# Power_24V.net
KiCad netlist of a schematic drawn in Altium Designer
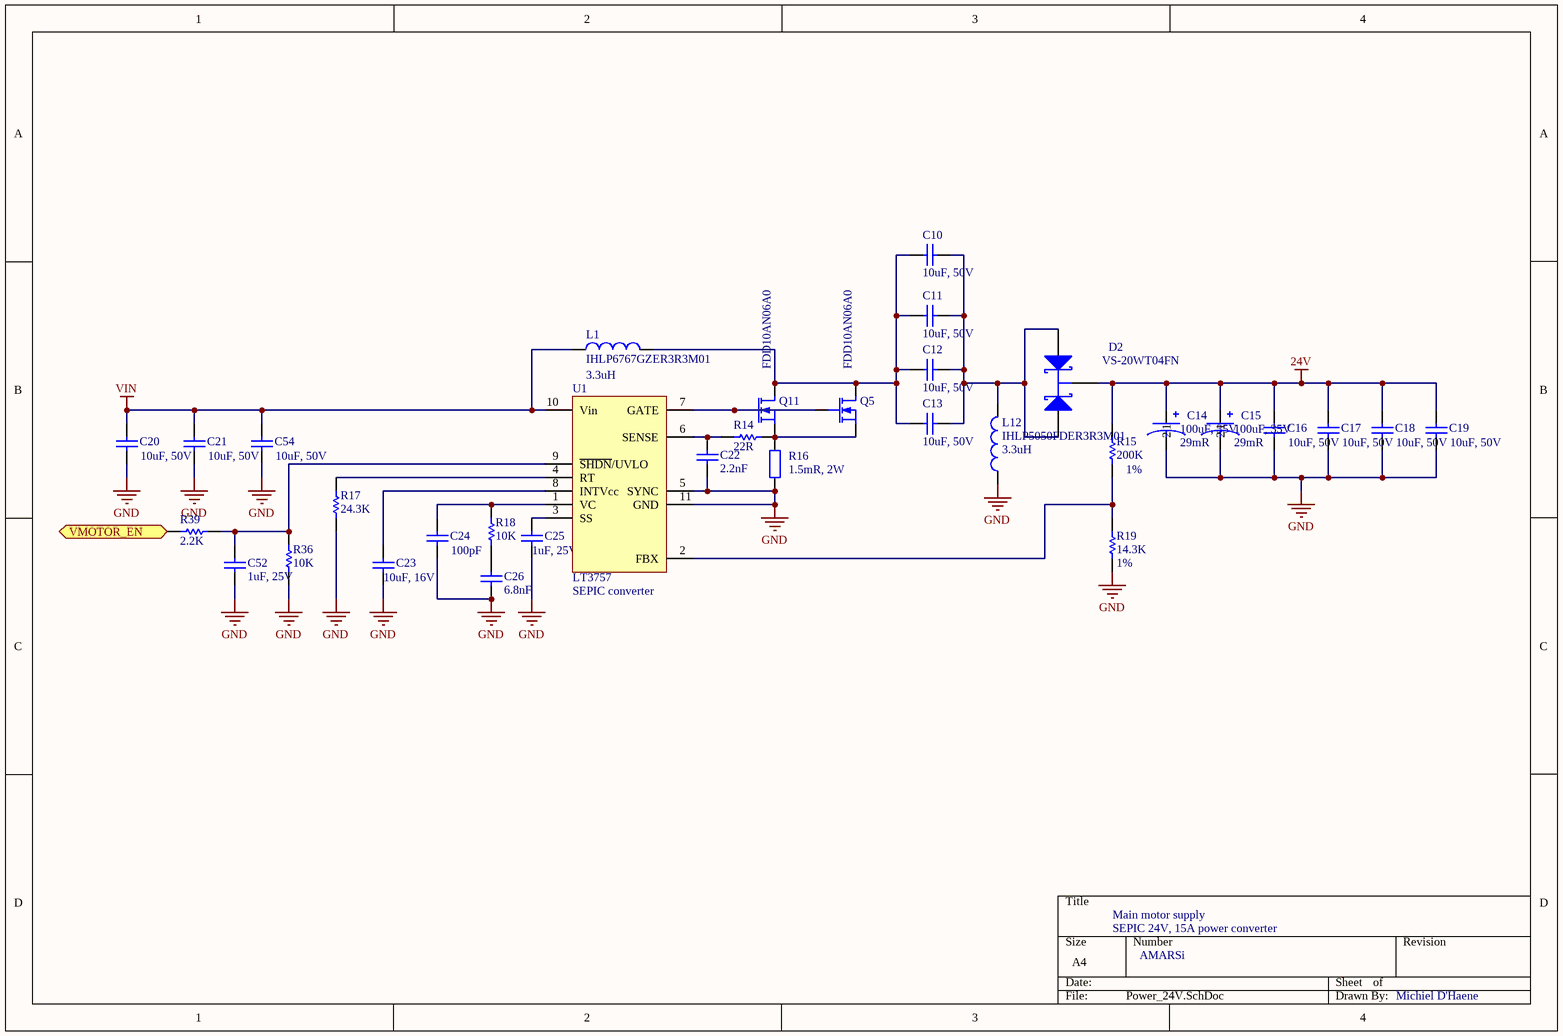
[diagram p0: Power_24V.SchDoc]

(export (version "E")
  (design (tool "Eeschema 10.0.6"))
  (components
    (comp (ref "C10")
      (value "10uF, 50V")
      (footprint "CAPC3216L")
      (description "Capacitor (Semiconductor SIM Model)")
      (fields (field (name "VOLTAGE") "50V") (field (name "PUBLISHER") "Altium Limited"))
      (libsource (lib "Miscellaneous Devices") (part "Cap Semi"))
    )
    (comp (ref "C11")
      (value "10uF, 50V")
      (footprint "CAPC3216L")
      (description "Capacitor (Semiconductor SIM Model)")
      (fields (field (name "VOLTAGE") "50V") (field (name "PUBLISHER") "Altium Limited"))
      (libsource (lib "Miscellaneous Devices") (part "Cap Semi"))
    )
    (comp (ref "C12")
      (value "10uF, 50V")
      (footprint "CAPC3216L")
      (description "Capacitor (Semiconductor SIM Model)")
      (fields (field (name "VOLTAGE") "50V") (field (name "PUBLISHER") "Altium Limited"))
      (libsource (lib "Miscellaneous Devices") (part "Cap Semi"))
    )
    (comp (ref "C13")
      (value "10uF, 50V")
      (footprint "CAPC3216L")
      (description "Capacitor (Semiconductor SIM Model)")
      (fields (field (name "VOLTAGE") "50V") (field (name "PUBLISHER") "Altium Limited"))
      (libsource (lib "Miscellaneous Devices") (part "Cap Semi"))
    )
    (comp (ref "C14")
      (value "100uF, 35V")
      (footprint "CAP_POL_SMD_SIZE_G")
      (fields (field (name "ESR") "29mR") (field (name "Comment") "100uF, 35V, 29mR"))
      (libsource (lib "New_library") (part "CAP_POL"))
    )
    (comp (ref "C15")
      (value "100uF, 35V")
      (footprint "CAP_POL_SMD_SIZE_G")
      (fields (field (name "ESR") "29mR") (field (name "Comment") "100uF, 35V, 29mR"))
      (libsource (lib "New_library") (part "CAP_POL"))
    )
    (comp (ref "C16")
      (value "10uF, 50V")
      (footprint "CAPC3216L")
      (description "Capacitor (Semiconductor SIM Model)")
      (fields (field (name "VOLTAGE") "50V") (field (name "PUBLISHER") "Altium Limited"))
      (libsource (lib "Miscellaneous Devices") (part "Cap Semi"))
    )
    (comp (ref "C17")
      (value "10uF, 50V")
      (footprint "CAPC3216L")
      (description "Capacitor (Semiconductor SIM Model)")
      (fields (field (name "VOLTAGE") "50V") (field (name "PUBLISHER") "Altium Limited"))
      (libsource (lib "Miscellaneous Devices") (part "Cap Semi"))
    )
    (comp (ref "C18")
      (value "10uF, 50V")
      (footprint "CAPC3216L")
      (description "Capacitor (Semiconductor SIM Model)")
      (fields (field (name "VOLTAGE") "50V") (field (name "PUBLISHER") "Altium Limited"))
      (libsource (lib "Miscellaneous Devices") (part "Cap Semi"))
    )
    (comp (ref "C19")
      (value "10uF, 50V")
      (footprint "CAPC3216L")
      (description "Capacitor (Semiconductor SIM Model)")
      (fields (field (name "VOLTAGE") "50V") (field (name "PUBLISHER") "Altium Limited"))
      (libsource (lib "Miscellaneous Devices") (part "Cap Semi"))
    )
    (comp (ref "C20")
      (value "10uF, 50V")
      (footprint "CAPC3216L")
      (description "Capacitor (Semiconductor SIM Model)")
      (fields (field (name "VOLTAGE") "50V") (field (name "PUBLISHER") "Altium Limited"))
      (libsource (lib "Miscellaneous Devices") (part "Cap Semi"))
    )
    (comp (ref "C21")
      (value "10uF, 50V")
      (footprint "CAPC3216L")
      (description "Capacitor (Semiconductor SIM Model)")
      (fields (field (name "VOLTAGE") "50V") (field (name "PUBLISHER") "Altium Limited"))
      (libsource (lib "Miscellaneous Devices") (part "Cap Semi"))
    )
    (comp (ref "C22")
      (value "2.2nF")
      (footprint "CAPC1608L")
      (description "Capacitor (Semiconductor SIM Model)")
      (fields (field (name "PUBLISHER") "Altium Limited"))
      (libsource (lib "Miscellaneous Devices") (part "Cap Semi"))
    )
    (comp (ref "C23")
      (value "10uF, 16V")
      (footprint "CAPC2512L")
      (description "Capacitor (Semiconductor SIM Model)")
      (fields (field (name "VOLTAGE") "10V") (field (name "PUBLISHER") "Altium Limited"))
      (libsource (lib "Miscellaneous Devices") (part "Cap Semi"))
    )
    (comp (ref "C24")
      (value "100pF")
      (footprint "CAPC1608L")
      (description "Capacitor")
      (fields (field (name "PUBLISHER") "Altium Limited"))
      (libsource (lib "Miscellaneous Devices") (part "Cap"))
    )
    (comp (ref "C25")
      (value "1uF, 25V")
      (footprint "CAPC1608L")
      (description "Capacitor")
      (fields (field (name "PUBLISHER") "Altium Limited"))
      (libsource (lib "Miscellaneous Devices") (part "Cap"))
    )
    (comp (ref "C26")
      (value "6.8nF")
      (footprint "CAPC1608L")
      (description "Capacitor")
      (fields (field (name "PUBLISHER") "Altium Limited"))
      (libsource (lib "Miscellaneous Devices") (part "Cap"))
    )
    (comp (ref "C52")
      (value "1uF, 25V")
      (footprint "CAPC1608L")
      (description "Capacitor (Semiconductor SIM Model)")
      (fields (field (name "PUBLISHER") "Altium Limited"))
      (libsource (lib "Miscellaneous Devices") (part "Cap Semi"))
    )
    (comp (ref "C54")
      (value "10uF, 50V")
      (footprint "CAPC3216L")
      (description "Capacitor (Semiconductor SIM Model)")
      (fields (field (name "VOLTAGE") "50V") (field (name "PUBLISHER") "Altium Limited"))
      (libsource (lib "Miscellaneous Devices") (part "Cap Semi"))
    )
    (comp (ref "D2")
      (value "VS-20WT04FN")
      (footprint "TO-252AA")
      (description "Schottky Rectifier")
      (fields (field (name "PUBLISHER") "Altium Limited"))
      (libsource (lib "IR Rectifier - Schottky") (part "12CWQ06FN"))
    )
    (comp (ref "L1")
      (value "IHLP6767GZER3R3M01")
      (footprint "IHLP-6767GZ")
      (fields (field (name "ALTIUM_VALUE") "3.3uH"))
      (libsource (lib "New_library") (part "Inductor"))
    )
    (comp (ref "L12")
      (value "IHLP5050FDER3R3M01")
      (footprint "IHLP5050")
      (description "Inductor")
      (fields (field (name "ALTIUM_VALUE") "3.3uH") (field (name "PUBLISHER") "Altium Limited"))
      (libsource (lib "Roombots") (part "Inductor"))
    )
    (comp (ref "Q5")
      (value "FDD10AN06A0")
      (footprint "TO-252A DPak")
      (description "N-Channel MOSFET")
      (libsource (lib "Roombots") (part "nFET"))
    )
    (comp (ref "Q11")
      (value "FDD10AN06A0")
      (footprint "TO-252A DPak")
      (description "N-Channel MOSFET")
      (libsource (lib "Roombots") (part "nFET"))
    )
    (comp (ref "R14")
      (value "22R")
      (footprint "RESC1608L")
      (description "Semiconductor Resistor")
      (fields (field (name "PUBLISHER") "Altium Limited"))
      (libsource (lib "Miscellaneous Devices") (part "Res Semi"))
    )
    (comp (ref "R15")
      (value "200K")
      (footprint "RESC1608L")
      (description "Semiconductor Resistor")
      (fields
        (field (name "PRECISION") "1%")
        (field (name "Comment") "200K, 1%")
        (field (name "PUBLISHER") "Altium Limited")
      )
      (libsource (lib "Miscellaneous Devices") (part "Res Semi"))
    )
    (comp (ref "R16")
      (value "1.5mR, 2W")
      (footprint "RESC6332N")
      (description "Resistor")
      (fields (field (name "PUBLISHER") "Altium Limited"))
      (libsource (lib "Miscellaneous Devices") (part "Res2"))
    )
    (comp (ref "R17")
      (value "24.3K")
      (footprint "RESC1608L")
      (description "Semiconductor Resistor")
      (fields (field (name "PUBLISHER") "Altium Limited"))
      (libsource (lib "Miscellaneous Devices") (part "Res Semi"))
    )
    (comp (ref "R18")
      (value "10K")
      (footprint "RESC1608L")
      (description "Semiconductor Resistor")
      (fields (field (name "PUBLISHER") "Altium Limited"))
      (libsource (lib "Miscellaneous Devices") (part "Res Semi"))
    )
    (comp (ref "R19")
      (value "14.3K")
      (footprint "RESC1608L")
      (description "Semiconductor Resistor")
      (fields
        (field (name "PRECISION") "1%")
        (field (name "Comment") "14.3K, 1%")
        (field (name "PUBLISHER") "Altium Limited")
      )
      (libsource (lib "Miscellaneous Devices") (part "Res Semi"))
    )
    (comp (ref "R36")
      (value "10K")
      (footprint "RESC1608L")
      (description "Semiconductor Resistor")
      (fields (field (name "PUBLISHER") "Altium Limited"))
      (libsource (lib "Miscellaneous Devices") (part "Res Semi"))
    )
    (comp (ref "R39")
      (value "2.2K")
      (footprint "RESC1608L")
      (description "Semiconductor Resistor")
      (fields (field (name "Comment") "2.2k") (field (name "PUBLISHER") "Altium Limited"))
      (libsource (lib "Miscellaneous Devices") (part "Res Semi"))
    )
    (comp (ref "U1")
      (value "LT3757")
      (footprint "MSOP-10-TP")
      (description "2.9-40V SEPIC, Flyback, Boost and Inverting Converter with external switch")
      (libsource (lib "Roombots") (part "LT3757"))
    )
  )
  (nets
    (net (code "1") (name "/VMOTOR_EN") (class "Default")
      (node (ref "R39") (pin "2") (pinfunction "2_2") (pintype "passive"))
    )
    (net (code "2") (name "24V") (class "Default")
      (node (ref "C14") (pin "2") (pinfunction "2_2") (pintype "passive"))
      (node (ref "C15") (pin "2") (pinfunction "2_2") (pintype "passive"))
      (node (ref "C16") (pin "2") (pinfunction "2_2") (pintype "passive"))
      (node (ref "C17") (pin "2") (pinfunction "2_2") (pintype "passive"))
      (node (ref "C18") (pin "2") (pinfunction "2_2") (pintype "passive"))
      (node (ref "C19") (pin "2") (pinfunction "2_2") (pintype "passive"))
      (node (ref "D2") (pin "4") (pinfunction "K_4") (pintype "passive"))
      (node (ref "R15") (pin "2") (pinfunction "2_2") (pintype "passive"))
    )
    (net (code "3") (name "GND") (class "Default")
      (node (ref "C14") (pin "1") (pinfunction "1_1") (pintype "passive"))
      (node (ref "C15") (pin "1") (pinfunction "1_1") (pintype "passive"))
      (node (ref "C16") (pin "1") (pinfunction "1_1") (pintype "passive"))
      (node (ref "C17") (pin "1") (pinfunction "1_1") (pintype "passive"))
      (node (ref "C18") (pin "1") (pinfunction "1_1") (pintype "passive"))
      (node (ref "C19") (pin "1") (pinfunction "1_1") (pintype "passive"))
      (node (ref "C20") (pin "1") (pinfunction "1_1") (pintype "passive"))
      (node (ref "C21") (pin "1") (pinfunction "1_1") (pintype "passive"))
      (node (ref "C22") (pin "1") (pinfunction "1_1") (pintype "passive"))
      (node (ref "C23") (pin "1") (pinfunction "1_1") (pintype "passive"))
      (node (ref "C24") (pin "1") (pinfunction "1_1") (pintype "passive"))
      (node (ref "C25") (pin "1") (pinfunction "1_1") (pintype "passive"))
      (node (ref "C26") (pin "1") (pinfunction "1_1") (pintype "passive"))
      (node (ref "C52") (pin "1") (pinfunction "1_1") (pintype "passive"))
      (node (ref "C54") (pin "1") (pinfunction "1_1") (pintype "passive"))
      (node (ref "L12") (pin "1") (pinfunction "1_1") (pintype "passive"))
      (node (ref "R16") (pin "1") (pinfunction "1_1") (pintype "passive"))
      (node (ref "R17") (pin "1") (pinfunction "1_1") (pintype "passive"))
      (node (ref "R19") (pin "1") (pinfunction "1_1") (pintype "passive"))
      (node (ref "R36") (pin "1") (pinfunction "1_1") (pintype "passive"))
      (node (ref "U1") (pin "11") (pinfunction "GND_11") (pintype "passive"))
      (node (ref "U1") (pin "5") (pinfunction "SYNC_5") (pintype "passive"))
    )
    (net (code "4") (name "Net-(C10-Pad2)") (class "Default")
      (node (ref "C10") (pin "2") (pinfunction "2_2") (pintype "passive"))
      (node (ref "C11") (pin "2") (pinfunction "2_2") (pintype "passive"))
      (node (ref "C12") (pin "2") (pinfunction "2_2") (pintype "passive"))
      (node (ref "C13") (pin "2") (pinfunction "2_2") (pintype "passive"))
      (node (ref "L1") (pin "2") (pinfunction "2_2") (pintype "passive"))
      (node (ref "Q11") (pin "D") (pinfunction "D_D") (pintype "passive"))
      (node (ref "Q5") (pin "D") (pinfunction "D_D") (pintype "passive"))
    )
    (net (code "5") (name "Net-(C26-Pad2)") (class "Default")
      (node (ref "C26") (pin "2") (pinfunction "2_2") (pintype "passive"))
      (node (ref "R18") (pin "1") (pinfunction "1_1") (pintype "passive"))
    )
    (net (code "6") (name "Net-(D2-A1)") (class "Default")
      (node (ref "C10") (pin "1") (pinfunction "1_1") (pintype "passive"))
      (node (ref "C11") (pin "1") (pinfunction "1_1") (pintype "passive"))
      (node (ref "C12") (pin "1") (pinfunction "1_1") (pintype "passive"))
      (node (ref "C13") (pin "1") (pinfunction "1_1") (pintype "passive"))
      (node (ref "D2") (pin "1") (pinfunction "A1_1") (pintype "passive"))
      (node (ref "D2") (pin "3") (pinfunction "A2_3") (pintype "passive"))
      (node (ref "L12") (pin "2") (pinfunction "2_2") (pintype "passive"))
    )
    (net (code "7") (name "Net-(Q11-PadS)") (class "Default")
      (node (ref "Q11") (pin "S") (pinfunction "S_S") (pintype "passive"))
      (node (ref "Q5") (pin "S") (pinfunction "S_S") (pintype "passive"))
      (node (ref "R14") (pin "2") (pinfunction "2_2") (pintype "passive"))
      (node (ref "R16") (pin "2") (pinfunction "2_2") (pintype "passive"))
    )
    (net (code "8") (name "Net-(U1-FBX)") (class "Default")
      (node (ref "R15") (pin "1") (pinfunction "1_1") (pintype "passive"))
      (node (ref "R19") (pin "2") (pinfunction "2_2") (pintype "passive"))
      (node (ref "U1") (pin "2") (pinfunction "FBX_2") (pintype "passive"))
    )
    (net (code "9") (name "Net-(U1-GATE)") (class "Default")
      (node (ref "Q11") (pin "G") (pinfunction "G_G") (pintype "passive"))
      (node (ref "Q5") (pin "G") (pinfunction "G_G") (pintype "passive"))
      (node (ref "U1") (pin "7") (pinfunction "GATE_7") (pintype "passive"))
    )
    (net (code "10") (name "Net-(U1-INTVcc)") (class "Default")
      (node (ref "C23") (pin "2") (pinfunction "2_2") (pintype "passive"))
      (node (ref "U1") (pin "8") (pinfunction "INTVcc_8") (pintype "passive"))
    )
    (net (code "11") (name "Net-(U1-RT)") (class "Default")
      (node (ref "R17") (pin "2") (pinfunction "2_2") (pintype "passive"))
      (node (ref "U1") (pin "4") (pinfunction "RT_4") (pintype "passive"))
    )
    (net (code "12") (name "Net-(U1-SENSE)") (class "Default")
      (node (ref "C22") (pin "2") (pinfunction "2_2") (pintype "passive"))
      (node (ref "R14") (pin "1") (pinfunction "1_1") (pintype "passive"))
      (node (ref "U1") (pin "6") (pinfunction "SENSE_6") (pintype "passive"))
    )
    (net (code "13") (name "Net-(U1-SS)") (class "Default")
      (node (ref "C25") (pin "2") (pinfunction "2_2") (pintype "passive"))
      (node (ref "U1") (pin "3") (pinfunction "SS_3") (pintype "passive"))
    )
    (net (code "14") (name "Net-(U1-VC)") (class "Default")
      (node (ref "C24") (pin "2") (pinfunction "2_2") (pintype "passive"))
      (node (ref "R18") (pin "2") (pinfunction "2_2") (pintype "passive"))
      (node (ref "U1") (pin "1") (pinfunction "VC_1") (pintype "passive"))
    )
    (net (code "15") (name "Net-(U1-~{SHDN}{slash}UVLO)") (class "Default")
      (node (ref "C52") (pin "2") (pinfunction "2_2") (pintype "passive"))
      (node (ref "R36") (pin "2") (pinfunction "2_2") (pintype "passive"))
      (node (ref "R39") (pin "1") (pinfunction "1_1") (pintype "passive"))
      (node (ref "U1") (pin "9") (pinfunction "~{SHDN}/UVLO_9") (pintype "passive"))
    )
    (net (code "16") (name "VIN") (class "Default")
      (node (ref "C20") (pin "2") (pinfunction "2_2") (pintype "passive"))
      (node (ref "C21") (pin "2") (pinfunction "2_2") (pintype "passive"))
      (node (ref "C54") (pin "2") (pinfunction "2_2") (pintype "passive"))
      (node (ref "L1") (pin "1") (pinfunction "1_1") (pintype "passive"))
      (node (ref "U1") (pin "10") (pinfunction "Vin_10") (pintype "passive"))
    )
  )
)
